# proto_shield_MEGA-REV3.net
KiCad netlist of a schematic drawn in EAGLE
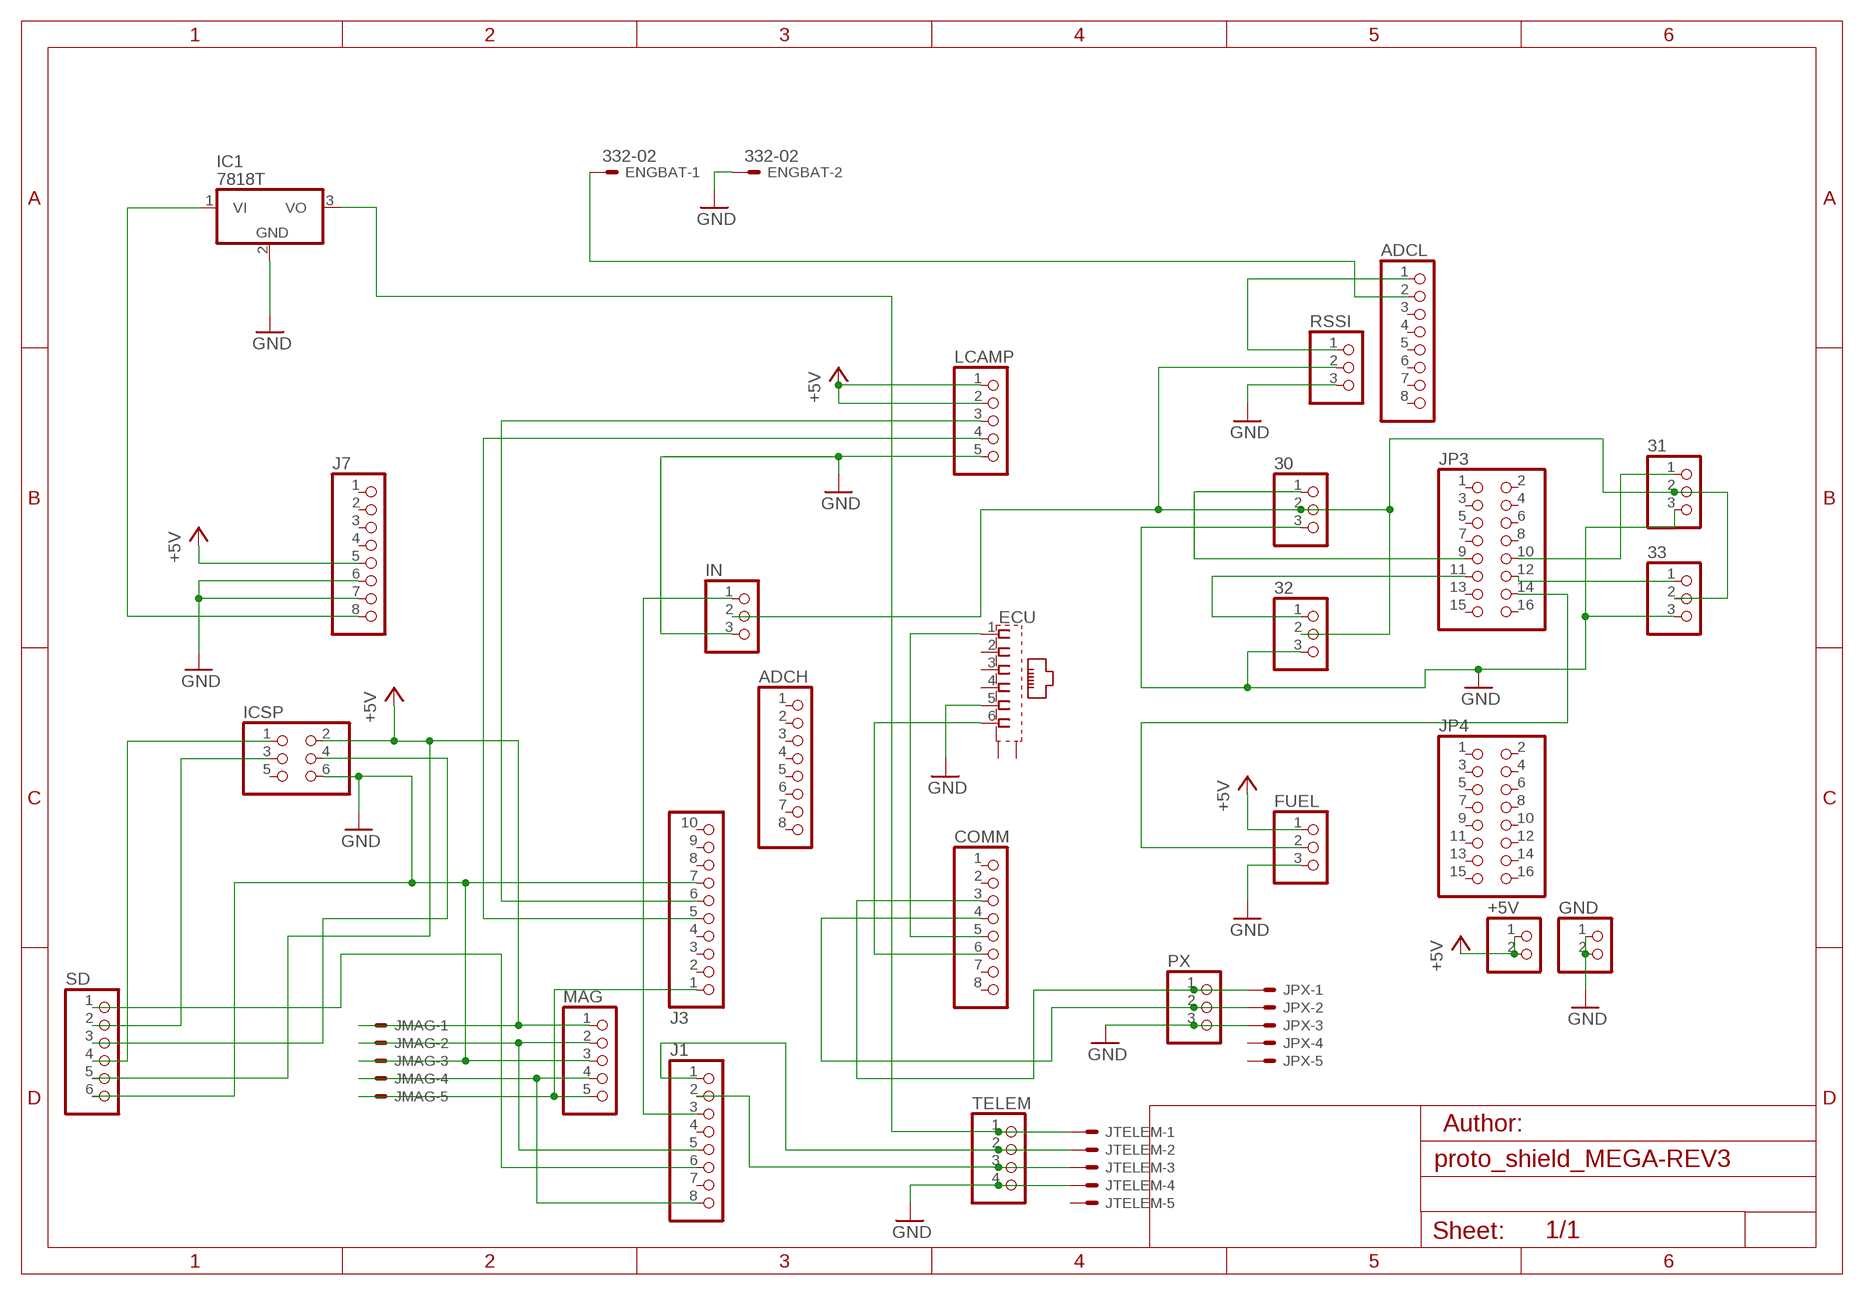
[diagram p0: schematic, sheet 1]

(export (version "E")
  (design (tool "Eeschema 10.0.6"))
  (components
    (comp (ref "+5V")
      (value "PINHD-1X2")
      (footprint "eagle-import:1X02")
      (libsource (lib "eagle-import") (part "PINHD-1X2"))
    )
    (comp (ref "30")
      (value "PINHD-1X3")
      (footprint "eagle-import:1X03")
      (libsource (lib "eagle-import") (part "PINHD-1X3"))
    )
    (comp (ref "31")
      (value "PINHD-1X3")
      (footprint "eagle-import:1X03")
      (libsource (lib "eagle-import") (part "PINHD-1X3"))
    )
    (comp (ref "32")
      (value "PINHD-1X3")
      (footprint "eagle-import:1X03")
      (libsource (lib "eagle-import") (part "PINHD-1X3"))
    )
    (comp (ref "33")
      (value "PINHD-1X3")
      (footprint "eagle-import:1X03")
      (libsource (lib "eagle-import") (part "PINHD-1X3"))
    )
    (comp (ref "ADCH")
      (value "PINHD-1X8TH")
      (footprint "eagle-import:1X08-TH")
      (libsource (lib "eagle-import") (part "PINHD-1X8TH"))
    )
    (comp (ref "ADCL")
      (value "PINHD-1X8TH")
      (footprint "eagle-import:1X08-TH")
      (libsource (lib "eagle-import") (part "PINHD-1X8TH"))
    )
    (comp (ref "COMM")
      (value "PINHD-1X8TH")
      (footprint "eagle-import:1X08-TH")
      (libsource (lib "eagle-import") (part "PINHD-1X8TH"))
    )
    (comp (ref "ECU")
      (value "XRJK-S-01-6-6-0-2G2-NO")
      (footprint "eagle-import:XRJK-S-01-6-6-0-2G2-NO")
      (libsource (lib "eagle-import") (part "XRJK6-0-2G2-NO-S-01-6-"))
    )
    (comp (ref "ENGBAT")
      (value "332-02")
      (footprint "eagle-import:332-02")
      (libsource (lib "eagle-import") (part "332-02"))
    )
    (comp (ref "FUEL")
      (value "PINHD-1X3")
      (footprint "eagle-import:1X03")
      (libsource (lib "eagle-import") (part "PINHD-1X3"))
    )
    (comp (ref "GND")
      (value "PINHD-1X2")
      (footprint "eagle-import:1X02")
      (libsource (lib "eagle-import") (part "PINHD-1X2"))
    )
    (comp (ref "IC1")
      (value "7818T")
      (footprint "eagle-import:TO220H")
      (libsource (lib "eagle-import") (part "78T18"))
    )
    (comp (ref "ICSP")
      (value "PINHD-2X3")
      (footprint "eagle-import:2X03")
      (libsource (lib "eagle-import") (part "PINHD-2X3"))
    )
    (comp (ref "IN")
      (value "PINHD-1X3")
      (footprint "eagle-import:1X03")
      (libsource (lib "eagle-import") (part "PINHD-1X3"))
    )
    (comp (ref "J1")
      (value "PINHD-1X8TH")
      (footprint "eagle-import:1X08-TH")
      (libsource (lib "eagle-import") (part "PINHD-1X8TH"))
    )
    (comp (ref "J3")
      (value "PINHD-1X10TH")
      (footprint "eagle-import:1X10-TH")
      (libsource (lib "eagle-import") (part "PINHD-1X10TH"))
    )
    (comp (ref "J7")
      (value "PINHD-1X8TH")
      (footprint "eagle-import:1X08-TH")
      (libsource (lib "eagle-import") (part "PINHD-1X8TH"))
    )
    (comp (ref "JMAG")
      (value "BM05B-SRSS-TB")
      (footprint "eagle-import:BM05B-SRSS-TB")
      (libsource (lib "eagle-import") (part "?M05B-SRSS-TBB"))
    )
    (comp (ref "JP3")
      (value "PINHD-2X8")
      (footprint "eagle-import:2X08")
      (libsource (lib "eagle-import") (part "PINHD-2X8"))
    )
    (comp (ref "JP4")
      (value "PINHD-2X8")
      (footprint "eagle-import:2X08")
      (libsource (lib "eagle-import") (part "PINHD-2X8"))
    )
    (comp (ref "JPX")
      (value "BM05B-SRSS-TB")
      (footprint "eagle-import:BM05B-SRSS-TB")
      (libsource (lib "eagle-import") (part "?M05B-SRSS-TBB"))
    )
    (comp (ref "JTELEM")
      (value "BM05B-SRSS-TB")
      (footprint "eagle-import:BM05B-SRSS-TB")
      (libsource (lib "eagle-import") (part "?M05B-SRSS-TBB"))
    )
    (comp (ref "LCAMP")
      (value "PINHD-1X5")
      (footprint "eagle-import:1X05")
      (libsource (lib "eagle-import") (part "PINHD-1X5"))
    )
    (comp (ref "MAG")
      (value "PINHD-1X5")
      (footprint "eagle-import:1X05")
      (libsource (lib "eagle-import") (part "PINHD-1X5"))
    )
    (comp (ref "PX")
      (value "PINHD-1X3")
      (footprint "eagle-import:1X03")
      (libsource (lib "eagle-import") (part "PINHD-1X3"))
    )
    (comp (ref "RSSI")
      (value "PINHD-1X3")
      (footprint "eagle-import:1X03")
      (libsource (lib "eagle-import") (part "PINHD-1X3"))
    )
    (comp (ref "SD")
      (value "PINHD-1X6")
      (footprint "eagle-import:1X06")
      (libsource (lib "eagle-import") (part "PINHD-1X6"))
    )
    (comp (ref "TELEM")
      (value "PINHD-1X4")
      (footprint "eagle-import:1X04")
      (libsource (lib "eagle-import") (part "PINHD-1X4"))
    )
  )
  (nets
    (net (code "1") (name "+5V") (class "Default")
      (node (ref "+5V") (pin "1") (pinfunction "1_1") (pintype "passive"))
      (node (ref "+5V") (pin "2") (pinfunction "2_2") (pintype "passive"))
      (node (ref "FUEL") (pin "1") (pinfunction "1_1") (pintype "passive"))
      (node (ref "ICSP") (pin "2") (pinfunction "2_2") (pintype "passive"))
      (node (ref "J7") (pin "5") (pinfunction "5_5") (pintype "passive"))
      (node (ref "JMAG") (pin "1") (pinfunction "S_1") (pintype "passive"))
      (node (ref "LCAMP") (pin "1") (pinfunction "1_1") (pintype "passive"))
      (node (ref "LCAMP") (pin "2") (pinfunction "2_2") (pintype "passive"))
      (node (ref "MAG") (pin "1") (pinfunction "1_1") (pintype "passive"))
      (node (ref "SD") (pin "5") (pinfunction "5_5") (pintype "passive"))
    )
    (net (code "2") (name "GND") (class "Default")
      (node (ref "30") (pin "3") (pinfunction "3_3") (pintype "passive"))
      (node (ref "31") (pin "3") (pinfunction "3_3") (pintype "passive"))
      (node (ref "32") (pin "3") (pinfunction "3_3") (pintype "passive"))
      (node (ref "33") (pin "3") (pinfunction "3_3") (pintype "passive"))
      (node (ref "ECU") (pin "5") (pinfunction "5_5") (pintype "passive"))
      (node (ref "ENGBAT") (pin "2") (pinfunction "S_2") (pintype "passive"))
      (node (ref "FUEL") (pin "3") (pinfunction "3_3") (pintype "passive"))
      (node (ref "GND") (pin "1") (pinfunction "1_1") (pintype "passive"))
      (node (ref "GND") (pin "2") (pinfunction "2_2") (pintype "passive"))
      (node (ref "IC1") (pin "2") (pinfunction "GND_2") (pintype "passive"))
      (node (ref "ICSP") (pin "6") (pinfunction "6_6") (pintype "passive"))
      (node (ref "IN") (pin "3") (pinfunction "3_3") (pintype "passive"))
      (node (ref "J3") (pin "7") (pinfunction "7_7") (pintype "passive"))
      (node (ref "J7") (pin "6") (pinfunction "6_6") (pintype "passive"))
      (node (ref "J7") (pin "7") (pinfunction "7_7") (pintype "passive"))
      (node (ref "JMAG") (pin "3") (pinfunction "S_3") (pintype "passive"))
      (node (ref "JPX") (pin "3") (pinfunction "S_3") (pintype "passive"))
      (node (ref "JTELEM") (pin "4") (pinfunction "S_4") (pintype "passive"))
      (node (ref "LCAMP") (pin "5") (pinfunction "5_5") (pintype "passive"))
      (node (ref "MAG") (pin "3") (pinfunction "3_3") (pintype "passive"))
      (node (ref "PX") (pin "3") (pinfunction "3_3") (pintype "passive"))
      (node (ref "RSSI") (pin "3") (pinfunction "3_3") (pintype "passive"))
      (node (ref "SD") (pin "6") (pinfunction "6_6") (pintype "passive"))
      (node (ref "TELEM") (pin "4") (pinfunction "4_4") (pintype "passive"))
    )
    (net (code "3") (name "Net-(30-Pad1)") (class "Default")
      (node (ref "30") (pin "1") (pinfunction "1_1") (pintype "passive"))
      (node (ref "JP3") (pin "9") (pinfunction "9_9") (pintype "passive"))
    )
    (net (code "4") (name "Net-(30-Pad2)") (class "Default")
      (node (ref "30") (pin "2") (pinfunction "2_2") (pintype "passive"))
      (node (ref "31") (pin "2") (pinfunction "2_2") (pintype "passive"))
      (node (ref "32") (pin "2") (pinfunction "2_2") (pintype "passive"))
      (node (ref "33") (pin "2") (pinfunction "2_2") (pintype "passive"))
      (node (ref "IN") (pin "2") (pinfunction "2_2") (pintype "passive"))
      (node (ref "RSSI") (pin "2") (pinfunction "2_2") (pintype "passive"))
    )
    (net (code "5") (name "Net-(31-Pad1)") (class "Default")
      (node (ref "31") (pin "1") (pinfunction "1_1") (pintype "passive"))
      (node (ref "JP3") (pin "10") (pinfunction "10_10") (pintype "passive"))
    )
    (net (code "6") (name "Net-(32-Pad1)") (class "Default")
      (node (ref "32") (pin "1") (pinfunction "1_1") (pintype "passive"))
      (node (ref "JP3") (pin "11") (pinfunction "11_11") (pintype "passive"))
    )
    (net (code "7") (name "Net-(33-Pad1)") (class "Default")
      (node (ref "33") (pin "1") (pinfunction "1_1") (pintype "passive"))
      (node (ref "JP3") (pin "12") (pinfunction "12_12") (pintype "passive"))
    )
    (net (code "8") (name "Net-(ADCL-Pad1)") (class "Default")
      (node (ref "ADCL") (pin "1") (pinfunction "1_1") (pintype "passive"))
      (node (ref "RSSI") (pin "1") (pinfunction "1_1") (pintype "passive"))
    )
    (net (code "9") (name "Net-(COMM-Pad5)") (class "Default")
      (node (ref "COMM") (pin "5") (pinfunction "5_5") (pintype "passive"))
      (node (ref "ECU") (pin "1") (pinfunction "1_1") (pintype "passive"))
    )
    (net (code "10") (name "Net-(COMM-Pad6)") (class "Default")
      (node (ref "COMM") (pin "6") (pinfunction "6_6") (pintype "passive"))
      (node (ref "ECU") (pin "6") (pinfunction "6_6") (pintype "passive"))
    )
    (net (code "11") (name "Net-(ENGBATA-S)") (class "Default")
      (node (ref "ADCL") (pin "2") (pinfunction "2_2") (pintype "passive"))
      (node (ref "ENGBAT") (pin "1") (pinfunction "S_1") (pintype "passive"))
    )
    (net (code "12") (name "Net-(FUEL-Pad2)") (class "Default")
      (node (ref "FUEL") (pin "2") (pinfunction "2_2") (pintype "passive"))
      (node (ref "JP3") (pin "14") (pinfunction "14_14") (pintype "passive"))
    )
    (net (code "13") (name "Net-(IC1-VI)") (class "Default")
      (node (ref "IC1") (pin "1") (pinfunction "VI_1") (pintype "input"))
      (node (ref "J7") (pin "8") (pinfunction "8_8") (pintype "passive"))
    )
    (net (code "14") (name "Net-(IC1-VO)") (class "Default")
      (node (ref "IC1") (pin "3") (pinfunction "VO_3") (pintype "passive"))
      (node (ref "JTELEM") (pin "1") (pinfunction "S_1") (pintype "passive"))
      (node (ref "TELEM") (pin "1") (pinfunction "1_1") (pintype "passive"))
    )
    (net (code "15") (name "Net-(ICSP-Pad1)") (class "Default")
      (node (ref "ICSP") (pin "1") (pinfunction "1_1") (pintype "passive"))
      (node (ref "SD") (pin "4") (pinfunction "4_4") (pintype "passive"))
    )
    (net (code "16") (name "Net-(ICSP-Pad3)") (class "Default")
      (node (ref "ICSP") (pin "3") (pinfunction "3_3") (pintype "passive"))
      (node (ref "SD") (pin "2") (pinfunction "2_2") (pintype "passive"))
    )
    (net (code "17") (name "Net-(ICSP-Pad4)") (class "Default")
      (node (ref "ICSP") (pin "4") (pinfunction "4_4") (pintype "passive"))
      (node (ref "SD") (pin "3") (pinfunction "3_3") (pintype "passive"))
    )
    (net (code "18") (name "Net-(IN-Pad1)") (class "Default")
      (node (ref "IN") (pin "1") (pinfunction "1_1") (pintype "passive"))
      (node (ref "J1") (pin "3") (pinfunction "3_3") (pintype "passive"))
    )
    (net (code "19") (name "Net-(J1-Pad6)") (class "Default")
      (node (ref "J1") (pin "6") (pinfunction "6_6") (pintype "passive"))
      (node (ref "SD") (pin "1") (pinfunction "1_1") (pintype "passive"))
    )
    (net (code "20") (name "Net-(J3-Pad5)") (class "Default")
      (node (ref "J3") (pin "5") (pinfunction "5_5") (pintype "passive"))
      (node (ref "LCAMP") (pin "4") (pinfunction "4_4") (pintype "passive"))
    )
    (net (code "21") (name "Net-(J3-Pad6)") (class "Default")
      (node (ref "J3") (pin "6") (pinfunction "6_6") (pintype "passive"))
      (node (ref "LCAMP") (pin "3") (pinfunction "3_3") (pintype "passive"))
    )
    (net (code "22") (name "Net-(JMAGB-S)") (class "Default")
      (node (ref "J1") (pin "5") (pinfunction "5_5") (pintype "passive"))
      (node (ref "JMAG") (pin "2") (pinfunction "S_2") (pintype "passive"))
      (node (ref "MAG") (pin "2") (pinfunction "2_2") (pintype "passive"))
    )
    (net (code "23") (name "Net-(JMAGD-S)") (class "Default")
      (node (ref "J1") (pin "8") (pinfunction "8_8") (pintype "passive"))
      (node (ref "JMAG") (pin "4") (pinfunction "S_4") (pintype "passive"))
      (node (ref "MAG") (pin "4") (pinfunction "4_4") (pintype "passive"))
    )
    (net (code "24") (name "Net-(JMAGE-S)") (class "Default")
      (node (ref "J3") (pin "1") (pinfunction "1_1") (pintype "passive"))
      (node (ref "JMAG") (pin "5") (pinfunction "S_5") (pintype "passive"))
      (node (ref "MAG") (pin "5") (pinfunction "5_5") (pintype "passive"))
    )
    (net (code "25") (name "Net-(JPXA-S)") (class "Default")
      (node (ref "COMM") (pin "3") (pinfunction "3_3") (pintype "passive"))
      (node (ref "JPX") (pin "1") (pinfunction "S_1") (pintype "passive"))
      (node (ref "PX") (pin "1") (pinfunction "1_1") (pintype "passive"))
    )
    (net (code "26") (name "Net-(JPXB-S)") (class "Default")
      (node (ref "COMM") (pin "4") (pinfunction "4_4") (pintype "passive"))
      (node (ref "JPX") (pin "2") (pinfunction "S_2") (pintype "passive"))
      (node (ref "PX") (pin "2") (pinfunction "2_2") (pintype "passive"))
    )
    (net (code "27") (name "Net-(JTELEMB-S)") (class "Default")
      (node (ref "J1") (pin "1") (pinfunction "1_1") (pintype "passive"))
      (node (ref "JTELEM") (pin "2") (pinfunction "S_2") (pintype "passive"))
      (node (ref "TELEM") (pin "2") (pinfunction "2_2") (pintype "passive"))
    )
    (net (code "28") (name "Net-(JTELEMC-S)") (class "Default")
      (node (ref "J1") (pin "2") (pinfunction "2_2") (pintype "passive"))
      (node (ref "JTELEM") (pin "3") (pinfunction "S_3") (pintype "passive"))
      (node (ref "TELEM") (pin "3") (pinfunction "3_3") (pintype "passive"))
    )
    (net (code "29") (name "unconnected-(ADCH-Pad1)") (class "Default")
      (node (ref "ADCH") (pin "1") (pinfunction "1_1") (pintype "passive"))
    )
    (net (code "30") (name "unconnected-(ADCH-Pad2)") (class "Default")
      (node (ref "ADCH") (pin "2") (pinfunction "2_2") (pintype "passive"))
    )
    (net (code "31") (name "unconnected-(ADCH-Pad3)") (class "Default")
      (node (ref "ADCH") (pin "3") (pinfunction "3_3") (pintype "passive"))
    )
    (net (code "32") (name "unconnected-(ADCH-Pad4)") (class "Default")
      (node (ref "ADCH") (pin "4") (pinfunction "4_4") (pintype "passive"))
    )
    (net (code "33") (name "unconnected-(ADCH-Pad5)") (class "Default")
      (node (ref "ADCH") (pin "5") (pinfunction "5_5") (pintype "passive"))
    )
    (net (code "34") (name "unconnected-(ADCH-Pad6)") (class "Default")
      (node (ref "ADCH") (pin "6") (pinfunction "6_6") (pintype "passive"))
    )
    (net (code "35") (name "unconnected-(ADCH-Pad7)") (class "Default")
      (node (ref "ADCH") (pin "7") (pinfunction "7_7") (pintype "passive"))
    )
    (net (code "36") (name "unconnected-(ADCH-Pad8)") (class "Default")
      (node (ref "ADCH") (pin "8") (pinfunction "8_8") (pintype "passive"))
    )
    (net (code "37") (name "unconnected-(ADCL-Pad3)") (class "Default")
      (node (ref "ADCL") (pin "3") (pinfunction "3_3") (pintype "passive"))
    )
    (net (code "38") (name "unconnected-(ADCL-Pad4)") (class "Default")
      (node (ref "ADCL") (pin "4") (pinfunction "4_4") (pintype "passive"))
    )
    (net (code "39") (name "unconnected-(ADCL-Pad5)") (class "Default")
      (node (ref "ADCL") (pin "5") (pinfunction "5_5") (pintype "passive"))
    )
    (net (code "40") (name "unconnected-(ADCL-Pad6)") (class "Default")
      (node (ref "ADCL") (pin "6") (pinfunction "6_6") (pintype "passive"))
    )
    (net (code "41") (name "unconnected-(ADCL-Pad7)") (class "Default")
      (node (ref "ADCL") (pin "7") (pinfunction "7_7") (pintype "passive"))
    )
    (net (code "42") (name "unconnected-(ADCL-Pad8)") (class "Default")
      (node (ref "ADCL") (pin "8") (pinfunction "8_8") (pintype "passive"))
    )
    (net (code "43") (name "unconnected-(COMM-Pad1)") (class "Default")
      (node (ref "COMM") (pin "1") (pinfunction "1_1") (pintype "passive"))
    )
    (net (code "44") (name "unconnected-(COMM-Pad2)") (class "Default")
      (node (ref "COMM") (pin "2") (pinfunction "2_2") (pintype "passive"))
    )
    (net (code "45") (name "unconnected-(COMM-Pad7)") (class "Default")
      (node (ref "COMM") (pin "7") (pinfunction "7_7") (pintype "passive"))
    )
    (net (code "46") (name "unconnected-(COMM-Pad8)") (class "Default")
      (node (ref "COMM") (pin "8") (pinfunction "8_8") (pintype "passive"))
    )
    (net (code "47") (name "unconnected-(ECU-Pad2)") (class "Default")
      (node (ref "ECU") (pin "2") (pinfunction "2_2") (pintype "passive"))
    )
    (net (code "48") (name "unconnected-(ECU-Pad3)") (class "Default")
      (node (ref "ECU") (pin "3") (pinfunction "3_3") (pintype "passive"))
    )
    (net (code "49") (name "unconnected-(ECU-Pad4)") (class "Default")
      (node (ref "ECU") (pin "4") (pinfunction "4_4") (pintype "passive"))
    )
    (net (code "50") (name "unconnected-(ECU-S-PadS1)") (class "Default")
      (node (ref "ECU") (pin "S1") (pinfunction "S_S1") (pintype "passive"))
    )
    (net (code "51") (name "unconnected-(ECU-S-PadS2)") (class "Default")
      (node (ref "ECU") (pin "S2") (pinfunction "S_S2") (pintype "passive"))
    )
    (net (code "52") (name "unconnected-(ICSP-Pad5)") (class "Default")
      (node (ref "ICSP") (pin "5") (pinfunction "5_5") (pintype "passive"))
    )
    (net (code "53") (name "unconnected-(J1-Pad4)") (class "Default")
      (node (ref "J1") (pin "4") (pinfunction "4_4") (pintype "passive"))
    )
    (net (code "54") (name "unconnected-(J1-Pad7)") (class "Default")
      (node (ref "J1") (pin "7") (pinfunction "7_7") (pintype "passive"))
    )
    (net (code "55") (name "unconnected-(J3-Pad2)") (class "Default")
      (node (ref "J3") (pin "2") (pinfunction "2_2") (pintype "passive"))
    )
    (net (code "56") (name "unconnected-(J3-Pad3)") (class "Default")
      (node (ref "J3") (pin "3") (pinfunction "3_3") (pintype "passive"))
    )
    (net (code "57") (name "unconnected-(J3-Pad4)") (class "Default")
      (node (ref "J3") (pin "4") (pinfunction "4_4") (pintype "passive"))
    )
    (net (code "58") (name "unconnected-(J3-Pad8)") (class "Default")
      (node (ref "J3") (pin "8") (pinfunction "8_8") (pintype "passive"))
    )
    (net (code "59") (name "unconnected-(J3-Pad9)") (class "Default")
      (node (ref "J3") (pin "9") (pinfunction "9_9") (pintype "passive"))
    )
    (net (code "60") (name "unconnected-(J3-Pad10)") (class "Default")
      (node (ref "J3") (pin "10") (pinfunction "10_10") (pintype "passive"))
    )
    (net (code "61") (name "unconnected-(J7-Pad1)") (class "Default")
      (node (ref "J7") (pin "1") (pinfunction "1_1") (pintype "passive"))
    )
    (net (code "62") (name "unconnected-(J7-Pad2)") (class "Default")
      (node (ref "J7") (pin "2") (pinfunction "2_2") (pintype "passive"))
    )
    (net (code "63") (name "unconnected-(J7-Pad3)") (class "Default")
      (node (ref "J7") (pin "3") (pinfunction "3_3") (pintype "passive"))
    )
    (net (code "64") (name "unconnected-(J7-Pad4)") (class "Default")
      (node (ref "J7") (pin "4") (pinfunction "4_4") (pintype "passive"))
    )
    (net (code "65") (name "unconnected-(JP3-Pad1)") (class "Default")
      (node (ref "JP3") (pin "1") (pinfunction "1_1") (pintype "passive"))
    )
    (net (code "66") (name "unconnected-(JP3-Pad2)") (class "Default")
      (node (ref "JP3") (pin "2") (pinfunction "2_2") (pintype "passive"))
    )
    (net (code "67") (name "unconnected-(JP3-Pad3)") (class "Default")
      (node (ref "JP3") (pin "3") (pinfunction "3_3") (pintype "passive"))
    )
    (net (code "68") (name "unconnected-(JP3-Pad4)") (class "Default")
      (node (ref "JP3") (pin "4") (pinfunction "4_4") (pintype "passive"))
    )
    (net (code "69") (name "unconnected-(JP3-Pad5)") (class "Default")
      (node (ref "JP3") (pin "5") (pinfunction "5_5") (pintype "passive"))
    )
    (net (code "70") (name "unconnected-(JP3-Pad6)") (class "Default")
      (node (ref "JP3") (pin "6") (pinfunction "6_6") (pintype "passive"))
    )
    (net (code "71") (name "unconnected-(JP3-Pad7)") (class "Default")
      (node (ref "JP3") (pin "7") (pinfunction "7_7") (pintype "passive"))
    )
    (net (code "72") (name "unconnected-(JP3-Pad8)") (class "Default")
      (node (ref "JP3") (pin "8") (pinfunction "8_8") (pintype "passive"))
    )
    (net (code "73") (name "unconnected-(JP3-Pad13)") (class "Default")
      (node (ref "JP3") (pin "13") (pinfunction "13_13") (pintype "passive"))
    )
    (net (code "74") (name "unconnected-(JP3-Pad15)") (class "Default")
      (node (ref "JP3") (pin "15") (pinfunction "15_15") (pintype "passive"))
    )
    (net (code "75") (name "unconnected-(JP3-Pad16)") (class "Default")
      (node (ref "JP3") (pin "16") (pinfunction "16_16") (pintype "passive"))
    )
    (net (code "76") (name "unconnected-(JP4-Pad1)") (class "Default")
      (node (ref "JP4") (pin "1") (pinfunction "1_1") (pintype "passive"))
    )
    (net (code "77") (name "unconnected-(JP4-Pad2)") (class "Default")
      (node (ref "JP4") (pin "2") (pinfunction "2_2") (pintype "passive"))
    )
    (net (code "78") (name "unconnected-(JP4-Pad3)") (class "Default")
      (node (ref "JP4") (pin "3") (pinfunction "3_3") (pintype "passive"))
    )
    (net (code "79") (name "unconnected-(JP4-Pad4)") (class "Default")
      (node (ref "JP4") (pin "4") (pinfunction "4_4") (pintype "passive"))
    )
    (net (code "80") (name "unconnected-(JP4-Pad5)") (class "Default")
      (node (ref "JP4") (pin "5") (pinfunction "5_5") (pintype "passive"))
    )
    (net (code "81") (name "unconnected-(JP4-Pad6)") (class "Default")
      (node (ref "JP4") (pin "6") (pinfunction "6_6") (pintype "passive"))
    )
    (net (code "82") (name "unconnected-(JP4-Pad7)") (class "Default")
      (node (ref "JP4") (pin "7") (pinfunction "7_7") (pintype "passive"))
    )
    (net (code "83") (name "unconnected-(JP4-Pad8)") (class "Default")
      (node (ref "JP4") (pin "8") (pinfunction "8_8") (pintype "passive"))
    )
    (net (code "84") (name "unconnected-(JP4-Pad9)") (class "Default")
      (node (ref "JP4") (pin "9") (pinfunction "9_9") (pintype "passive"))
    )
    (net (code "85") (name "unconnected-(JP4-Pad10)") (class "Default")
      (node (ref "JP4") (pin "10") (pinfunction "10_10") (pintype "passive"))
    )
    (net (code "86") (name "unconnected-(JP4-Pad11)") (class "Default")
      (node (ref "JP4") (pin "11") (pinfunction "11_11") (pintype "passive"))
    )
    (net (code "87") (name "unconnected-(JP4-Pad12)") (class "Default")
      (node (ref "JP4") (pin "12") (pinfunction "12_12") (pintype "passive"))
    )
    (net (code "88") (name "unconnected-(JP4-Pad13)") (class "Default")
      (node (ref "JP4") (pin "13") (pinfunction "13_13") (pintype "passive"))
    )
    (net (code "89") (name "unconnected-(JP4-Pad14)") (class "Default")
      (node (ref "JP4") (pin "14") (pinfunction "14_14") (pintype "passive"))
    )
    (net (code "90") (name "unconnected-(JP4-Pad15)") (class "Default")
      (node (ref "JP4") (pin "15") (pinfunction "15_15") (pintype "passive"))
    )
    (net (code "91") (name "unconnected-(JP4-Pad16)") (class "Default")
      (node (ref "JP4") (pin "16") (pinfunction "16_16") (pintype "passive"))
    )
    (net (code "92") (name "unconnected-(JPXD-S-Pad4)") (class "Default")
      (node (ref "JPX") (pin "4") (pinfunction "S_4") (pintype "passive"))
    )
    (net (code "93") (name "unconnected-(JPXE-S-Pad5)") (class "Default")
      (node (ref "JPX") (pin "5") (pinfunction "S_5") (pintype "passive"))
    )
    (net (code "94") (name "unconnected-(JTELEME-S-Pad5)") (class "Default")
      (node (ref "JTELEM") (pin "5") (pinfunction "S_5") (pintype "passive"))
    )
  )
)
